# 7_esc.net
KiCad netlist of a schematic drawn in Altium Designer
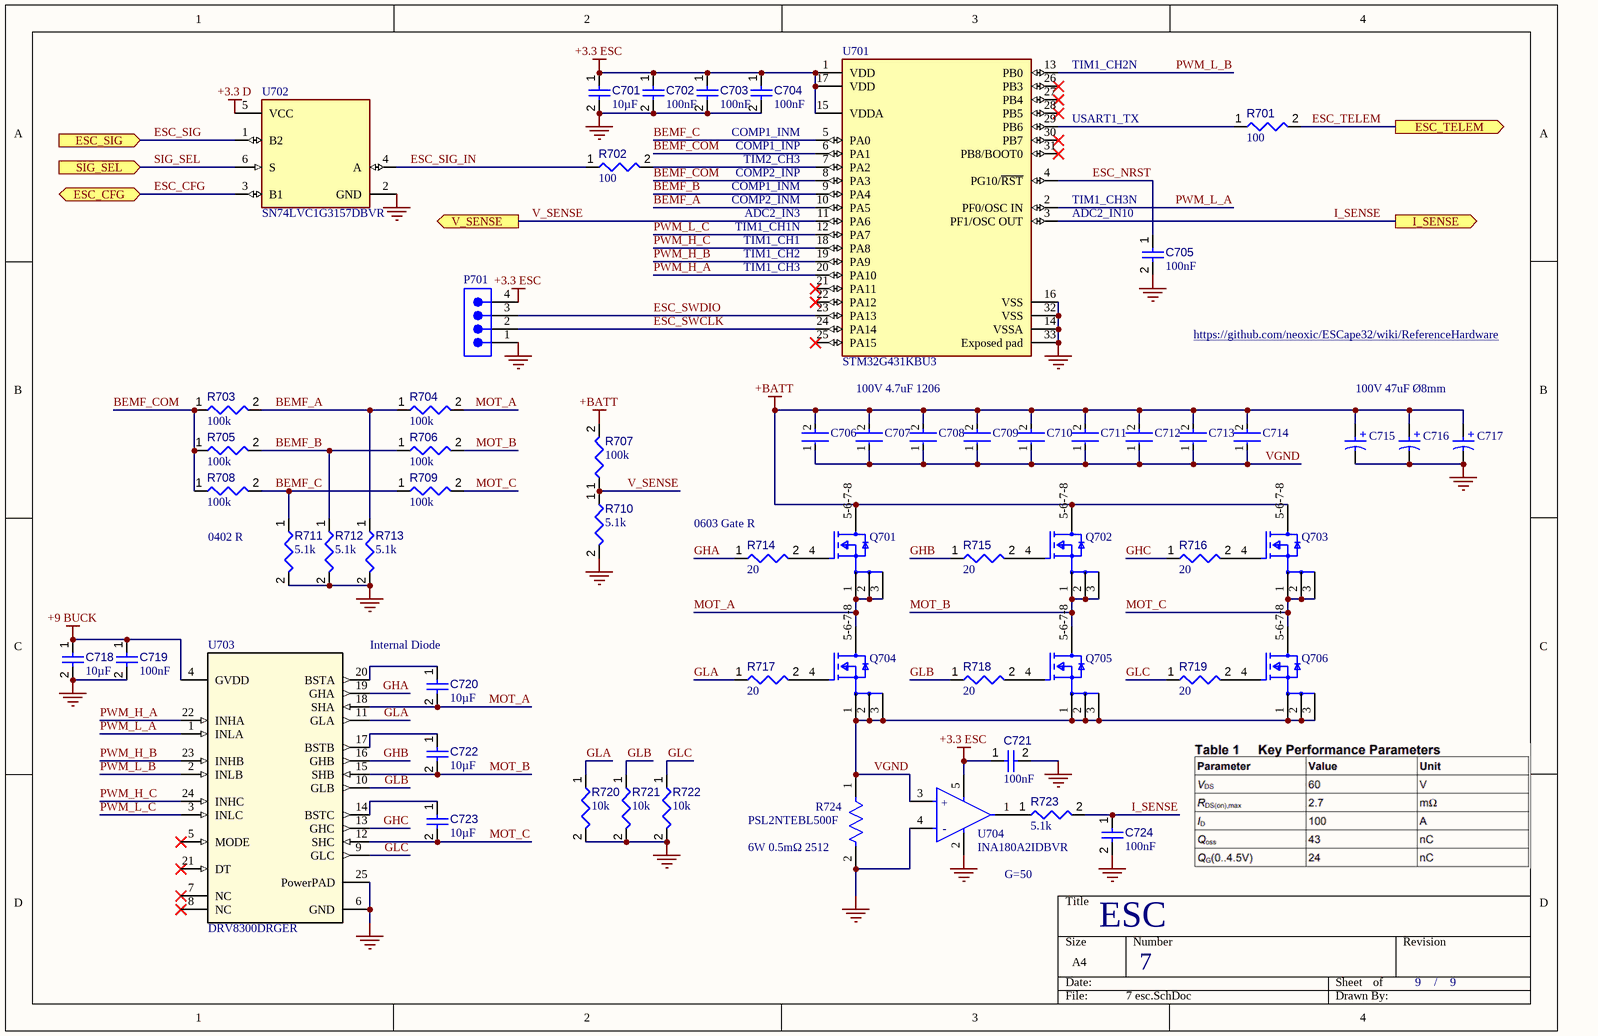
[diagram p0: 7 esc.SchDoc]

(export (version "E")
  (design (tool "Eeschema 10.0.6"))
  (components
    (comp (ref "C701")
      (value "10µF")
      (footprint "CAPC0603(1608)100_L")
      (description "Chip Capacitor, 10µF +/-20%, 10V, 0603, Thickness 1 mm")
      (fields (field (name "TOLERANCE") "10%") (field (name "Comment") "Capacitor 10µF +/-20% 10V 0603"))
      (libsource (lib "UBC Uncrewed Aircraft Systems") (part "CAP-NP-2"))
    )
    (comp (ref "C702")
      (value "100nF")
      (footprint "CAPC0402(1005)60_L")
      (description "Chip Capacitor, 100nF +/-20%, 25V, 0402, Thickness 0.6 mm")
      (fields (field (name "TOLERANCE") "10%") (field (name "Comment") "Capacitor 100nF +/-20% 25V 0402"))
      (libsource (lib "UBC Uncrewed Aircraft Systems") (part "CAP-NP-2"))
    )
    (comp (ref "C703")
      (value "100nF")
      (footprint "CAPC0402(1005)60_L")
      (description "Chip Capacitor, 100nF +/-20%, 25V, 0402, Thickness 0.6 mm")
      (fields (field (name "TOLERANCE") "10%") (field (name "Comment") "Capacitor 100nF +/-20% 25V 0402"))
      (libsource (lib "UBC Uncrewed Aircraft Systems") (part "CAP-NP-2"))
    )
    (comp (ref "C704")
      (value "100nF")
      (footprint "CAPC0402(1005)60_L")
      (description "Chip Capacitor, 100nF +/-20%, 25V, 0402, Thickness 0.6 mm")
      (fields (field (name "TOLERANCE") "10%") (field (name "Comment") "Capacitor 100nF +/-20% 25V 0402"))
      (libsource (lib "UBC Uncrewed Aircraft Systems") (part "CAP-NP-2"))
    )
    (comp (ref "C705")
      (value "100nF")
      (footprint "CAPC0402(1005)60_L")
      (description "Chip Capacitor, 100nF +/-20%, 25V, 0402, Thickness 0.6 mm")
      (fields (field (name "TOLERANCE") "10%") (field (name "Comment") "Capacitor 100nF +/-20% 25V 0402"))
      (libsource (lib "UBC Uncrewed Aircraft Systems") (part "CAP-NP-2"))
    )
    (comp (ref "C706")
      (value "GRM31CZ72A475KE11L")
      (footprint "FP-GRM31C-0_3-e0_3_0_9-MFG")
      (description "Chip Multilayer Ceramic Capacitors for General Purpose, 1206, 4.7uF, X7R, 15%, 10%, 100V")
      (libsource (lib "Altium Content Vault") (part "f23184f103b6ebe33a8c269c53dcba6"))
    )
    (comp (ref "C707")
      (value "GRM31CZ72A475KE11L")
      (footprint "FP-GRM31C-0_3-e0_3_0_9-MFG")
      (description "Chip Multilayer Ceramic Capacitors for General Purpose, 1206, 4.7uF, X7R, 15%, 10%, 100V")
      (libsource (lib "Altium Content Vault") (part "f23184f103b6ebe33a8c269c53dcba6"))
    )
    (comp (ref "C708")
      (value "GRM31CZ72A475KE11L")
      (footprint "FP-GRM31C-0_3-e0_3_0_9-MFG")
      (description "Chip Multilayer Ceramic Capacitors for General Purpose, 1206, 4.7uF, X7R, 15%, 10%, 100V")
      (libsource (lib "Altium Content Vault") (part "f23184f103b6ebe33a8c269c53dcba6"))
    )
    (comp (ref "C709")
      (value "GRM31CZ72A475KE11L")
      (footprint "FP-GRM31C-0_3-e0_3_0_9-MFG")
      (description "Chip Multilayer Ceramic Capacitors for General Purpose, 1206, 4.7uF, X7R, 15%, 10%, 100V")
      (libsource (lib "Altium Content Vault") (part "f23184f103b6ebe33a8c269c53dcba6"))
    )
    (comp (ref "C710")
      (value "GRM31CZ72A475KE11L")
      (footprint "FP-GRM31C-0_3-e0_3_0_9-MFG")
      (description "Chip Multilayer Ceramic Capacitors for General Purpose, 1206, 4.7uF, X7R, 15%, 10%, 100V")
      (libsource (lib "Altium Content Vault") (part "f23184f103b6ebe33a8c269c53dcba6"))
    )
    (comp (ref "C711")
      (value "GRM31CZ72A475KE11L")
      (footprint "FP-GRM31C-0_3-e0_3_0_9-MFG")
      (description "Chip Multilayer Ceramic Capacitors for General Purpose, 1206, 4.7uF, X7R, 15%, 10%, 100V")
      (libsource (lib "Altium Content Vault") (part "f23184f103b6ebe33a8c269c53dcba6"))
    )
    (comp (ref "C712")
      (value "GRM31CZ72A475KE11L")
      (footprint "FP-GRM31C-0_3-e0_3_0_9-MFG")
      (description "Chip Multilayer Ceramic Capacitors for General Purpose, 1206, 4.7uF, X7R, 15%, 10%, 100V")
      (libsource (lib "Altium Content Vault") (part "f23184f103b6ebe33a8c269c53dcba6"))
    )
    (comp (ref "C713")
      (value "GRM31CZ72A475KE11L")
      (footprint "FP-GRM31C-0_3-e0_3_0_9-MFG")
      (description "Chip Multilayer Ceramic Capacitors for General Purpose, 1206, 4.7uF, X7R, 15%, 10%, 100V")
      (libsource (lib "Altium Content Vault") (part "f23184f103b6ebe33a8c269c53dcba6"))
    )
    (comp (ref "C714")
      (value "GRM31CZ72A475KE11L")
      (footprint "FP-GRM31C-0_3-e0_3_0_9-MFG")
      (description "Chip Multilayer Ceramic Capacitors for General Purpose, 1206, 4.7uF, X7R, 15%, 10%, 100V")
      (libsource (lib "Altium Content Vault") (part "f23184f103b6ebe33a8c269c53dcba6"))
    )
    (comp (ref "C715")
      (value "865230453006")
      (footprint "WCAP-AS5H_D8H10.5")
      (description "865230453006 WCAP-AS5H Aluminum Electrolytic Capacitors")
      (fields (field (name "TOLERANCE") "20%"))
      (libsource (lib "Altium Content Vault") (part "Capacitor_Polarized"))
    )
    (comp (ref "C716")
      (value "865230453006")
      (footprint "WCAP-AS5H_D8H10.5")
      (description "865230453006 WCAP-AS5H Aluminum Electrolytic Capacitors")
      (fields (field (name "TOLERANCE") "20%"))
      (libsource (lib "Altium Content Vault") (part "Capacitor_Polarized"))
    )
    (comp (ref "C717")
      (value "865230453006")
      (footprint "WCAP-AS5H_D8H10.5")
      (description "865230453006 WCAP-AS5H Aluminum Electrolytic Capacitors")
      (fields (field (name "TOLERANCE") "20%"))
      (libsource (lib "Altium Content Vault") (part "Capacitor_Polarized"))
    )
    (comp (ref "C718")
      (value "10µF")
      (footprint "CAPC0603(1608)100_L")
      (description "Chip Capacitor, 10µF +/-20%, 10V, 0603, Thickness 1 mm")
      (fields (field (name "TOLERANCE") "10%") (field (name "Comment") "Capacitor 10µF +/-20% 10V 0603"))
      (libsource (lib "UBC Uncrewed Aircraft Systems") (part "CAP-NP-2"))
    )
    (comp (ref "C719")
      (value "100nF")
      (footprint "CAPC0402(1005)60_L")
      (description "Chip Capacitor, 100nF +/-20%, 25V, 0402, Thickness 0.6 mm")
      (fields (field (name "TOLERANCE") "10%") (field (name "Comment") "Capacitor 100nF +/-20% 25V 0402"))
      (libsource (lib "UBC Uncrewed Aircraft Systems") (part "CAP-NP-2"))
    )
    (comp (ref "C720")
      (value "10µF")
      (footprint "CAPC0603(1608)100_L")
      (description "Chip Capacitor, 10µF +/-20%, 10V, 0603, Thickness 1 mm")
      (fields (field (name "TOLERANCE") "10%") (field (name "Comment") "Capacitor 10µF +/-20% 10V 0603"))
      (libsource (lib "UBC Uncrewed Aircraft Systems") (part "CAP-NP-2"))
    )
    (comp (ref "C721")
      (value "100nF")
      (footprint "CAPC0402(1005)60_L")
      (description "Chip Capacitor, 100nF +/-20%, 25V, 0402, Thickness 0.6 mm")
      (fields (field (name "TOLERANCE") "10%") (field (name "Comment") "Capacitor 100nF +/-20% 25V 0402"))
      (libsource (lib "UBC Uncrewed Aircraft Systems") (part "CAP-NP-2"))
    )
    (comp (ref "C722")
      (value "10µF")
      (footprint "CAPC0603(1608)100_L")
      (description "Chip Capacitor, 10µF +/-20%, 10V, 0603, Thickness 1 mm")
      (fields (field (name "TOLERANCE") "10%") (field (name "Comment") "Capacitor 10µF +/-20% 10V 0603"))
      (libsource (lib "UBC Uncrewed Aircraft Systems") (part "CAP-NP-2"))
    )
    (comp (ref "C723")
      (value "10µF")
      (footprint "CAPC0603(1608)100_L")
      (description "Chip Capacitor, 10µF +/-20%, 10V, 0603, Thickness 1 mm")
      (fields (field (name "TOLERANCE") "10%") (field (name "Comment") "Capacitor 10µF +/-20% 10V 0603"))
      (libsource (lib "UBC Uncrewed Aircraft Systems") (part "CAP-NP-2"))
    )
    (comp (ref "C724")
      (value "100nF")
      (footprint "CAPC0402(1005)60_L")
      (description "Chip Capacitor, 100nF +/-20%, 25V, 0402, Thickness 0.6 mm")
      (fields (field (name "TOLERANCE") "10%") (field (name "Comment") "Capacitor 100nF +/-20% 25V 0402"))
      (libsource (lib "UBC Uncrewed Aircraft Systems") (part "CAP-NP-2"))
    )
    (comp (ref "P701")
      (value "61300411121")
      (footprint "61300411121")
      (libsource (lib "Altium Content Vault") (part "Header_Male_1R_04P"))
    )
    (comp (ref "Q701")
      (value "BSC0702LSATMA1")
      (footprint "FP-PG-TDSON-8-MFG")
      (description "BSC0702LSATMA1 Transistor MOSFET N-CH 60V 100A 8-Pin TDSON T/R - Tape and Reel")
      (libsource (lib "Altium Content Vault") (part "02f5e2c6ae375491c3e768752663af3"))
    )
    (comp (ref "Q702")
      (value "BSC0702LSATMA1")
      (footprint "FP-PG-TDSON-8-MFG")
      (description "BSC0702LSATMA1 Transistor MOSFET N-CH 60V 100A 8-Pin TDSON T/R - Tape and Reel")
      (libsource (lib "Altium Content Vault") (part "02f5e2c6ae375491c3e768752663af3"))
    )
    (comp (ref "Q703")
      (value "BSC0702LSATMA1")
      (footprint "FP-PG-TDSON-8-MFG")
      (description "BSC0702LSATMA1 Transistor MOSFET N-CH 60V 100A 8-Pin TDSON T/R - Tape and Reel")
      (libsource (lib "Altium Content Vault") (part "02f5e2c6ae375491c3e768752663af3"))
    )
    (comp (ref "Q704")
      (value "BSC0702LSATMA1")
      (footprint "FP-PG-TDSON-8-MFG")
      (description "BSC0702LSATMA1 Transistor MOSFET N-CH 60V 100A 8-Pin TDSON T/R - Tape and Reel")
      (libsource (lib "Altium Content Vault") (part "02f5e2c6ae375491c3e768752663af3"))
    )
    (comp (ref "Q705")
      (value "BSC0702LSATMA1")
      (footprint "FP-PG-TDSON-8-MFG")
      (description "BSC0702LSATMA1 Transistor MOSFET N-CH 60V 100A 8-Pin TDSON T/R - Tape and Reel")
      (libsource (lib "Altium Content Vault") (part "02f5e2c6ae375491c3e768752663af3"))
    )
    (comp (ref "Q706")
      (value "BSC0702LSATMA1")
      (footprint "FP-PG-TDSON-8-MFG")
      (description "BSC0702LSATMA1 Transistor MOSFET N-CH 60V 100A 8-Pin TDSON T/R - Tape and Reel")
      (libsource (lib "Altium Content Vault") (part "02f5e2c6ae375491c3e768752663af3"))
    )
    (comp (ref "R701")
      (value "100")
      (footprint "RESC0402(1005)_L")
      (description "Chip Resistor, 100 Ohms, +/-1 %, 63 mW, -55 to 155 degC, 0402")
      (fields (field (name "POWER") "63mW") (field (name "TOLERANCE") "1%"))
      (libsource (lib "UBC Uncrewed Aircraft Systems") (part "RES-2"))
    )
    (comp (ref "R702")
      (value "100")
      (footprint "RESC0402(1005)_L")
      (description "Chip Resistor, 100 Ohms, +/-1 %, 63 mW, -55 to 155 degC, 0402")
      (fields (field (name "POWER") "63mW") (field (name "TOLERANCE") "1%"))
      (libsource (lib "UBC Uncrewed Aircraft Systems") (part "RES-2"))
    )
    (comp (ref "R703")
      (value "100k")
      (footprint "RESC0402(1005)_L")
      (description "Chip Resistor, 100 kOhms, +/-1 %, 63 mW, -55 to 155 degC, 0402")
      (fields (field (name "TOLERANCE") "1%") (field (name "POWER") "63mW"))
      (libsource (lib "UBC Uncrewed Aircraft Systems") (part "RES-2"))
    )
    (comp (ref "R704")
      (value "100k")
      (footprint "RESC0402(1005)_L")
      (description "Chip Resistor, 100 kOhms, +/-1 %, 63 mW, -55 to 155 degC, 0402")
      (fields (field (name "TOLERANCE") "1%") (field (name "POWER") "63mW"))
      (libsource (lib "UBC Uncrewed Aircraft Systems") (part "RES-2"))
    )
    (comp (ref "R705")
      (value "100k")
      (footprint "RESC0402(1005)_L")
      (description "Chip Resistor, 100 kOhms, +/-1 %, 63 mW, -55 to 155 degC, 0402")
      (fields (field (name "TOLERANCE") "1%") (field (name "POWER") "63mW"))
      (libsource (lib "UBC Uncrewed Aircraft Systems") (part "RES-2"))
    )
    (comp (ref "R706")
      (value "100k")
      (footprint "RESC0402(1005)_L")
      (description "Chip Resistor, 100 kOhms, +/-1 %, 63 mW, -55 to 155 degC, 0402")
      (fields (field (name "TOLERANCE") "1%") (field (name "POWER") "63mW"))
      (libsource (lib "UBC Uncrewed Aircraft Systems") (part "RES-2"))
    )
    (comp (ref "R707")
      (value "100k")
      (footprint "RESC0402(1005)_L")
      (description "Chip Resistor, 100 kOhms, +/-1 %, 63 mW, -55 to 155 degC, 0402")
      (fields (field (name "TOLERANCE") "1%") (field (name "POWER") "63mW"))
      (libsource (lib "UBC Uncrewed Aircraft Systems") (part "RES-2"))
    )
    (comp (ref "R708")
      (value "100k")
      (footprint "RESC0402(1005)_L")
      (description "Chip Resistor, 100 kOhms, +/-1 %, 63 mW, -55 to 155 degC, 0402")
      (fields (field (name "TOLERANCE") "1%") (field (name "POWER") "63mW"))
      (libsource (lib "UBC Uncrewed Aircraft Systems") (part "RES-2"))
    )
    (comp (ref "R709")
      (value "100k")
      (footprint "RESC0402(1005)_L")
      (description "Chip Resistor, 100 kOhms, +/-1 %, 63 mW, -55 to 155 degC, 0402")
      (fields (field (name "TOLERANCE") "1%") (field (name "POWER") "63mW"))
      (libsource (lib "UBC Uncrewed Aircraft Systems") (part "RES-2"))
    )
    (comp (ref "R710")
      (value "5.1k")
      (footprint "RESC0402(1005)_L")
      (description "Chip Resistor, 5.1 kOhms, +/-1 %, 63 mW, -55 to 155 degC, 0402")
      (fields (field (name "POWER") "63mW") (field (name "TOLERANCE") "1%"))
      (libsource (lib "UBC Uncrewed Aircraft Systems") (part "RES-2"))
    )
    (comp (ref "R711")
      (value "5.1k")
      (footprint "RESC0402(1005)_L")
      (description "Chip Resistor, 5.1 kOhms, +/-1 %, 63 mW, -55 to 155 degC, 0402")
      (fields (field (name "POWER") "63mW") (field (name "TOLERANCE") "1%"))
      (libsource (lib "UBC Uncrewed Aircraft Systems") (part "RES-2"))
    )
    (comp (ref "R712")
      (value "5.1k")
      (footprint "RESC0402(1005)_L")
      (description "Chip Resistor, 5.1 kOhms, +/-1 %, 63 mW, -55 to 155 degC, 0402")
      (fields (field (name "POWER") "63mW") (field (name "TOLERANCE") "1%"))
      (libsource (lib "UBC Uncrewed Aircraft Systems") (part "RES-2"))
    )
    (comp (ref "R713")
      (value "5.1k")
      (footprint "RESC0402(1005)_L")
      (description "Chip Resistor, 5.1 kOhms, +/-1 %, 63 mW, -55 to 155 degC, 0402")
      (fields (field (name "POWER") "63mW") (field (name "TOLERANCE") "1%"))
      (libsource (lib "UBC Uncrewed Aircraft Systems") (part "RES-2"))
    )
    (comp (ref "R714")
      (value "20")
      (footprint "RESC0603(1608)_L")
      (description "Chip Resistor, 20 Ohms, +/-5 %, 0.1 W, -55 to 155 degC, 0603")
      (fields (field (name "TOLERANCE") "5%") (field (name "POWER") "100mW"))
      (libsource (lib "UBC Uncrewed Aircraft Systems") (part "RES-2"))
    )
    (comp (ref "R715")
      (value "20")
      (footprint "RESC0603(1608)_L")
      (description "Chip Resistor, 20 Ohms, +/-5 %, 0.1 W, -55 to 155 degC, 0603")
      (fields (field (name "TOLERANCE") "5%") (field (name "POWER") "100mW"))
      (libsource (lib "UBC Uncrewed Aircraft Systems") (part "RES-2"))
    )
    (comp (ref "R716")
      (value "20")
      (footprint "RESC0603(1608)_L")
      (description "Chip Resistor, 20 Ohms, +/-5 %, 0.1 W, -55 to 155 degC, 0603")
      (fields (field (name "TOLERANCE") "5%") (field (name "POWER") "100mW"))
      (libsource (lib "UBC Uncrewed Aircraft Systems") (part "RES-2"))
    )
    (comp (ref "R717")
      (value "20")
      (footprint "RESC0603(1608)_L")
      (description "Chip Resistor, 20 Ohms, +/-5 %, 0.1 W, -55 to 155 degC, 0603")
      (fields (field (name "TOLERANCE") "5%") (field (name "POWER") "100mW"))
      (libsource (lib "UBC Uncrewed Aircraft Systems") (part "RES-2"))
    )
    (comp (ref "R718")
      (value "20")
      (footprint "RESC0603(1608)_L")
      (description "Chip Resistor, 20 Ohms, +/-5 %, 0.1 W, -55 to 155 degC, 0603")
      (fields (field (name "TOLERANCE") "5%") (field (name "POWER") "100mW"))
      (libsource (lib "UBC Uncrewed Aircraft Systems") (part "RES-2"))
    )
    (comp (ref "R719")
      (value "20")
      (footprint "RESC0603(1608)_L")
      (description "Chip Resistor, 20 Ohms, +/-5 %, 0.1 W, -55 to 155 degC, 0603")
      (fields (field (name "TOLERANCE") "5%") (field (name "POWER") "100mW"))
      (libsource (lib "UBC Uncrewed Aircraft Systems") (part "RES-2"))
    )
    (comp (ref "R720")
      (value "10k")
      (footprint "RESC0402(1005)_L")
      (description "Chip Resistor, 10 kOhms, +/-1 %, 63 mW, -55 to 125 degC, 0402")
      (fields (field (name "POWER") "63mW") (field (name "TOLERANCE") "1%"))
      (libsource (lib "UBC Uncrewed Aircraft Systems") (part "RES-2"))
    )
    (comp (ref "R721")
      (value "10k")
      (footprint "RESC0402(1005)_L")
      (description "Chip Resistor, 10 kOhms, +/-1 %, 63 mW, -55 to 125 degC, 0402")
      (fields (field (name "POWER") "63mW") (field (name "TOLERANCE") "1%"))
      (libsource (lib "UBC Uncrewed Aircraft Systems") (part "RES-2"))
    )
    (comp (ref "R722")
      (value "10k")
      (footprint "RESC0402(1005)_L")
      (description "Chip Resistor, 10 kOhms, +/-1 %, 63 mW, -55 to 125 degC, 0402")
      (fields (field (name "POWER") "63mW") (field (name "TOLERANCE") "1%"))
      (libsource (lib "UBC Uncrewed Aircraft Systems") (part "RES-2"))
    )
    (comp (ref "R723")
      (value "5.1k")
      (footprint "RESC0402(1005)_L")
      (description "Chip Resistor, 5.1 kOhms, +/-1 %, 63 mW, -55 to 155 degC, 0402")
      (fields (field (name "POWER") "63mW") (field (name "TOLERANCE") "1%"))
      (libsource (lib "UBC Uncrewed Aircraft Systems") (part "RES-2"))
    )
    (comp (ref "R724")
      (value "PSL2NTEBL500F")
      (footprint "FP-PSL2NTEBL500F-MFG")
      (description "RES 500 UOHM 1% 8W NONSTANDARD")
      (libsource (lib "Altium Content Vault") (part "1029c3af85768c4190bb7ad29bc67b5"))
    )
    (comp (ref "U701")
      (value "STM32G431KBU3")
      (footprint "FP-UFQFPN32-A0B8-MFG")
      (description "IC MCU 32BIT 128KB FLSH 32UFQFPN")
      (libsource (lib "Altium Content Vault") (part "b0f9ef315fadbc83d4ed39e8b05710e"))
    )
    (comp (ref "U702")
      (value "SN74LVC1G3157DBVR")
      (footprint "FP-DBV0006A-IPC_C")
      (description "IC SWITCH SPDT SOT23-6")
      (libsource (lib "Altium Content Vault") (part "14cfcf06f1431fbc89496e2a44d6624"))
    )
    (comp (ref "U703")
      (value "DRV8300DRGER")
      (footprint "RGE0024B-MFG")
      (description "No Description Available")
      (libsource (lib "DRV8300DRGER") (part "DRV8300DRGER"))
    )
    (comp (ref "U704")
      (value "INA180A2IDBVR")
      (footprint "FP-DBV0005A-MFG")
      (description "IC CURR SENSE 1 CIRCUIT SOT23-5")
      (libsource (lib "Altium Content Vault") (part "0a55cf1a948ad01a3239aec1b7efad0"))
    )
  )
  (nets
    (net (code "1") (name "+3.3 D") (class "Default")
      (node (ref "U702") (pin "5") (pinfunction "VCC_5") (pintype "power_in"))
    )
    (net (code "2") (name "+3.3 ESC") (class "Default")
      (node (ref "C701") (pin "1") (pinfunction "1_1") (pintype "passive"))
      (node (ref "C702") (pin "1") (pinfunction "1_1") (pintype "passive"))
      (node (ref "C703") (pin "1") (pinfunction "1_1") (pintype "passive"))
      (node (ref "C704") (pin "1") (pinfunction "1_1") (pintype "passive"))
      (node (ref "C721") (pin "1") (pinfunction "1_1") (pintype "passive"))
      (node (ref "P701") (pin "4") (pinfunction "4_4") (pintype "passive"))
      (node (ref "U701") (pin "1") (pinfunction "VDD_1") (pintype "power_in"))
      (node (ref "U701") (pin "15") (pinfunction "VDDA_15") (pintype "power_in"))
      (node (ref "U701") (pin "17") (pinfunction "VDD_17") (pintype "power_in"))
      (node (ref "U704") (pin "5") (pinfunction "VS_5") (pintype "power_in"))
    )
    (net (code "3") (name "+9 BUCK") (class "Default")
      (node (ref "C718") (pin "1") (pinfunction "1_1") (pintype "passive"))
      (node (ref "C719") (pin "1") (pinfunction "1_1") (pintype "passive"))
      (node (ref "U703") (pin "4") (pinfunction "GVDD_4") (pintype "power_in"))
    )
    (net (code "4") (name "+BATT") (class "Default")
      (node (ref "C706") (pin "2") (pinfunction "2_2") (pintype "passive"))
      (node (ref "C707") (pin "2") (pinfunction "2_2") (pintype "passive"))
      (node (ref "C708") (pin "2") (pinfunction "2_2") (pintype "passive"))
      (node (ref "C709") (pin "2") (pinfunction "2_2") (pintype "passive"))
      (node (ref "C710") (pin "2") (pinfunction "2_2") (pintype "passive"))
      (node (ref "C711") (pin "2") (pinfunction "2_2") (pintype "passive"))
      (node (ref "C712") (pin "2") (pinfunction "2_2") (pintype "passive"))
      (node (ref "C713") (pin "2") (pinfunction "2_2") (pintype "passive"))
      (node (ref "C714") (pin "2") (pinfunction "2_2") (pintype "passive"))
      (node (ref "C715") (pin "1") (pinfunction "P_1") (pintype "passive"))
      (node (ref "C716") (pin "1") (pinfunction "P_1") (pintype "passive"))
      (node (ref "C717") (pin "1") (pinfunction "P_1") (pintype "passive"))
      (node (ref "Q701") (pin "5-6-7-8") (pinfunction "Drain_5-6-7-8") (pintype "passive"))
      (node (ref "Q702") (pin "5-6-7-8") (pinfunction "Drain_5-6-7-8") (pintype "passive"))
      (node (ref "Q703") (pin "5-6-7-8") (pinfunction "Drain_5-6-7-8") (pintype "passive"))
      (node (ref "R707") (pin "2") (pinfunction "2_2") (pintype "passive"))
    )
    (net (code "5") (name "/BEMF_A") (class "Default")
      (node (ref "R703") (pin "2") (pinfunction "2_2") (pintype "passive"))
      (node (ref "R704") (pin "1") (pinfunction "1_1") (pintype "passive"))
      (node (ref "R713") (pin "1") (pinfunction "1_1") (pintype "passive"))
      (node (ref "U701") (pin "10") (pinfunction "PA5_10") (pintype "bidirectional"))
    )
    (net (code "6") (name "/BEMF_B") (class "Default")
      (node (ref "R705") (pin "2") (pinfunction "2_2") (pintype "passive"))
      (node (ref "R706") (pin "1") (pinfunction "1_1") (pintype "passive"))
      (node (ref "R712") (pin "1") (pinfunction "1_1") (pintype "passive"))
      (node (ref "U701") (pin "9") (pinfunction "PA4_9") (pintype "bidirectional"))
    )
    (net (code "7") (name "/BEMF_C") (class "Default")
      (node (ref "R708") (pin "2") (pinfunction "2_2") (pintype "passive"))
      (node (ref "R709") (pin "1") (pinfunction "1_1") (pintype "passive"))
      (node (ref "R711") (pin "1") (pinfunction "1_1") (pintype "passive"))
      (node (ref "U701") (pin "5") (pinfunction "PA0_5") (pintype "bidirectional"))
    )
    (net (code "8") (name "/BEMF_COM") (class "Default")
      (node (ref "R703") (pin "1") (pinfunction "1_1") (pintype "passive"))
      (node (ref "R705") (pin "1") (pinfunction "1_1") (pintype "passive"))
      (node (ref "R708") (pin "1") (pinfunction "1_1") (pintype "passive"))
      (node (ref "U701") (pin "6") (pinfunction "PA1_6") (pintype "bidirectional"))
      (node (ref "U701") (pin "8") (pinfunction "PA3_8") (pintype "bidirectional"))
    )
    (net (code "9") (name "/ESC_CFG") (class "Default")
      (node (ref "U702") (pin "3") (pinfunction "B1_3") (pintype "bidirectional"))
    )
    (net (code "10") (name "/ESC_NRST") (class "Default")
      (node (ref "C705") (pin "1") (pinfunction "1_1") (pintype "passive"))
      (node (ref "U701") (pin "4") (pinfunction "PG10/~{RST}_4") (pintype "bidirectional"))
    )
    (net (code "11") (name "/ESC_SIG") (class "Default")
      (node (ref "U702") (pin "1") (pinfunction "B2_1") (pintype "bidirectional"))
    )
    (net (code "12") (name "/ESC_SIG_IN") (class "Default")
      (node (ref "R702") (pin "1") (pinfunction "1_1") (pintype "passive"))
      (node (ref "U702") (pin "4") (pinfunction "A_4") (pintype "bidirectional"))
    )
    (net (code "13") (name "/ESC_SWCLK") (class "Default")
      (node (ref "P701") (pin "2") (pinfunction "2_2") (pintype "passive"))
      (node (ref "U701") (pin "24") (pinfunction "PA14_24") (pintype "bidirectional"))
    )
    (net (code "14") (name "/ESC_SWDIO") (class "Default")
      (node (ref "P701") (pin "3") (pinfunction "3_3") (pintype "passive"))
      (node (ref "U701") (pin "23") (pinfunction "PA13_23") (pintype "bidirectional"))
    )
    (net (code "15") (name "/ESC_TELEM") (class "Default")
      (node (ref "R701") (pin "2") (pinfunction "2_2") (pintype "passive"))
    )
    (net (code "16") (name "/GHA") (class "Default")
      (node (ref "R714") (pin "1") (pinfunction "1_1") (pintype "passive"))
      (node (ref "U703") (pin "19") (pinfunction "GHA_19") (pintype "output"))
    )
    (net (code "17") (name "/GHB") (class "Default")
      (node (ref "R715") (pin "1") (pinfunction "1_1") (pintype "passive"))
      (node (ref "U703") (pin "16") (pinfunction "GHB_16") (pintype "output"))
    )
    (net (code "18") (name "/GHC") (class "Default")
      (node (ref "R716") (pin "1") (pinfunction "1_1") (pintype "passive"))
      (node (ref "U703") (pin "13") (pinfunction "GHC_13") (pintype "output"))
    )
    (net (code "19") (name "/GLA") (class "Default")
      (node (ref "R717") (pin "1") (pinfunction "1_1") (pintype "passive"))
      (node (ref "R720") (pin "1") (pinfunction "1_1") (pintype "passive"))
      (node (ref "U703") (pin "11") (pinfunction "GLA_11") (pintype "output"))
    )
    (net (code "20") (name "/GLB") (class "Default")
      (node (ref "R718") (pin "1") (pinfunction "1_1") (pintype "passive"))
      (node (ref "R721") (pin "1") (pinfunction "1_1") (pintype "passive"))
      (node (ref "U703") (pin "10") (pinfunction "GLB_10") (pintype "output"))
    )
    (net (code "21") (name "/GLC") (class "Default")
      (node (ref "R719") (pin "1") (pinfunction "1_1") (pintype "passive"))
      (node (ref "R722") (pin "1") (pinfunction "1_1") (pintype "passive"))
      (node (ref "U703") (pin "9") (pinfunction "GLC_9") (pintype "output"))
    )
    (net (code "22") (name "/I_SENSE") (class "Default")
      (node (ref "C724") (pin "1") (pinfunction "1_1") (pintype "passive"))
      (node (ref "R723") (pin "2") (pinfunction "2_2") (pintype "passive"))
      (node (ref "U701") (pin "3") (pinfunction "PF1/OSC_OUT_3") (pintype "bidirectional"))
    )
    (net (code "23") (name "/MOT_A") (class "Default")
      (node (ref "C720") (pin "2") (pinfunction "2_2") (pintype "passive"))
      (node (ref "Q701") (pin "1") (pinfunction "Source_1") (pintype "passive"))
      (node (ref "Q701") (pin "2") (pinfunction "Source_2") (pintype "passive"))
      (node (ref "Q701") (pin "3") (pinfunction "Source_3") (pintype "passive"))
      (node (ref "Q704") (pin "5-6-7-8") (pinfunction "Drain_5-6-7-8") (pintype "passive"))
      (node (ref "R704") (pin "2") (pinfunction "2_2") (pintype "passive"))
      (node (ref "U703") (pin "18") (pinfunction "SHA_18") (pintype "input"))
    )
    (net (code "24") (name "/MOT_B") (class "Default")
      (node (ref "C722") (pin "2") (pinfunction "2_2") (pintype "passive"))
      (node (ref "Q702") (pin "1") (pinfunction "Source_1") (pintype "passive"))
      (node (ref "Q702") (pin "2") (pinfunction "Source_2") (pintype "passive"))
      (node (ref "Q702") (pin "3") (pinfunction "Source_3") (pintype "passive"))
      (node (ref "Q705") (pin "5-6-7-8") (pinfunction "Drain_5-6-7-8") (pintype "passive"))
      (node (ref "R706") (pin "2") (pinfunction "2_2") (pintype "passive"))
      (node (ref "U703") (pin "15") (pinfunction "SHB_15") (pintype "input"))
    )
    (net (code "25") (name "/MOT_C") (class "Default")
      (node (ref "C723") (pin "2") (pinfunction "2_2") (pintype "passive"))
      (node (ref "Q703") (pin "1") (pinfunction "Source_1") (pintype "passive"))
      (node (ref "Q703") (pin "2") (pinfunction "Source_2") (pintype "passive"))
      (node (ref "Q703") (pin "3") (pinfunction "Source_3") (pintype "passive"))
      (node (ref "Q706") (pin "5-6-7-8") (pinfunction "Drain_5-6-7-8") (pintype "passive"))
      (node (ref "R709") (pin "2") (pinfunction "2_2") (pintype "passive"))
      (node (ref "U703") (pin "12") (pinfunction "SHC_12") (pintype "input"))
    )
    (net (code "26") (name "/PWM_H_A") (class "Default")
      (node (ref "U701") (pin "20") (pinfunction "PA10_20") (pintype "bidirectional"))
      (node (ref "U703") (pin "22") (pinfunction "INHA_22") (pintype "input"))
    )
    (net (code "27") (name "/PWM_H_B") (class "Default")
      (node (ref "U701") (pin "19") (pinfunction "PA9_19") (pintype "bidirectional"))
      (node (ref "U703") (pin "23") (pinfunction "INHB_23") (pintype "input"))
    )
    (net (code "28") (name "/PWM_H_C") (class "Default")
      (node (ref "U701") (pin "18") (pinfunction "PA8_18") (pintype "bidirectional"))
      (node (ref "U703") (pin "24") (pinfunction "INHC_24") (pintype "input"))
    )
    (net (code "29") (name "/PWM_L_A") (class "Default")
      (node (ref "U701") (pin "2") (pinfunction "PF0/OSC_IN_2") (pintype "bidirectional"))
      (node (ref "U703") (pin "1") (pinfunction "INLA_1") (pintype "input"))
    )
    (net (code "30") (name "/PWM_L_B") (class "Default")
      (node (ref "U701") (pin "13") (pinfunction "PB0_13") (pintype "bidirectional"))
      (node (ref "U703") (pin "2") (pinfunction "INLB_2") (pintype "input"))
    )
    (net (code "31") (name "/PWM_L_C") (class "Default")
      (node (ref "U701") (pin "12") (pinfunction "PA7_12") (pintype "bidirectional"))
      (node (ref "U703") (pin "3") (pinfunction "INLC_3") (pintype "input"))
    )
    (net (code "32") (name "/SIG_SEL") (class "Default")
      (node (ref "U702") (pin "6") (pinfunction "S_6") (pintype "input"))
    )
    (net (code "33") (name "/VGND") (class "Default")
      (node (ref "C706") (pin "1") (pinfunction "1_1") (pintype "passive"))
      (node (ref "C707") (pin "1") (pinfunction "1_1") (pintype "passive"))
      (node (ref "C708") (pin "1") (pinfunction "1_1") (pintype "passive"))
      (node (ref "C709") (pin "1") (pinfunction "1_1") (pintype "passive"))
      (node (ref "C710") (pin "1") (pinfunction "1_1") (pintype "passive"))
      (node (ref "C711") (pin "1") (pinfunction "1_1") (pintype "passive"))
      (node (ref "C712") (pin "1") (pinfunction "1_1") (pintype "passive"))
      (node (ref "C713") (pin "1") (pinfunction "1_1") (pintype "passive"))
      (node (ref "C714") (pin "1") (pinfunction "1_1") (pintype "passive"))
      (node (ref "Q704") (pin "1") (pinfunction "Source_1") (pintype "passive"))
      (node (ref "Q704") (pin "2") (pinfunction "Source_2") (pintype "passive"))
      (node (ref "Q704") (pin "3") (pinfunction "Source_3") (pintype "passive"))
      (node (ref "Q705") (pin "1") (pinfunction "Source_1") (pintype "passive"))
      (node (ref "Q705") (pin "2") (pinfunction "Source_2") (pintype "passive"))
      (node (ref "Q705") (pin "3") (pinfunction "Source_3") (pintype "passive"))
      (node (ref "Q706") (pin "1") (pinfunction "Source_1") (pintype "passive"))
      (node (ref "Q706") (pin "2") (pinfunction "Source_2") (pintype "passive"))
      (node (ref "Q706") (pin "3") (pinfunction "Source_3") (pintype "passive"))
      (node (ref "R724") (pin "1") (pinfunction "1_1") (pintype "passive"))
      (node (ref "U704") (pin "3") (pinfunction "IN+_3") (pintype "tri_state"))
    )
    (net (code "34") (name "/V_SENSE") (class "Default")
      (node (ref "R707") (pin "1") (pinfunction "1_1") (pintype "passive"))
      (node (ref "R710") (pin "1") (pinfunction "1_1") (pintype "passive"))
      (node (ref "U701") (pin "11") (pinfunction "PA6_11") (pintype "bidirectional"))
    )
    (net (code "35") (name "GND") (class "Default")
      (node (ref "C701") (pin "2") (pinfunction "2_2") (pintype "passive"))
      (node (ref "C702") (pin "2") (pinfunction "2_2") (pintype "passive"))
      (node (ref "C703") (pin "2") (pinfunction "2_2") (pintype "passive"))
      (node (ref "C704") (pin "2") (pinfunction "2_2") (pintype "passive"))
      (node (ref "C705") (pin "2") (pinfunction "2_2") (pintype "passive"))
      (node (ref "C715") (pin "2") (pinfunction "N_2") (pintype "passive"))
      (node (ref "C716") (pin "2") (pinfunction "N_2") (pintype "passive"))
      (node (ref "C717") (pin "2") (pinfunction "N_2") (pintype "passive"))
      (node (ref "C718") (pin "2") (pinfunction "2_2") (pintype "passive"))
      (node (ref "C719") (pin "2") (pinfunction "2_2") (pintype "passive"))
      (node (ref "C721") (pin "2") (pinfunction "2_2") (pintype "passive"))
      (node (ref "C724") (pin "2") (pinfunction "2_2") (pintype "passive"))
      (node (ref "P701") (pin "1") (pinfunction "1_1") (pintype "passive"))
      (node (ref "R710") (pin "2") (pinfunction "2_2") (pintype "passive"))
      (node (ref "R711") (pin "2") (pinfunction "2_2") (pintype "passive"))
      (node (ref "R712") (pin "2") (pinfunction "2_2") (pintype "passive"))
      (node (ref "R713") (pin "2") (pinfunction "2_2") (pintype "passive"))
      (node (ref "R720") (pin "2") (pinfunction "2_2") (pintype "passive"))
      (node (ref "R721") (pin "2") (pinfunction "2_2") (pintype "passive"))
      (node (ref "R722") (pin "2") (pinfunction "2_2") (pintype "passive"))
      (node (ref "R724") (pin "2") (pinfunction "2_2") (pintype "passive"))
      (node (ref "U701") (pin "14") (pinfunction "VSSA_14") (pintype "power_in"))
      (node (ref "U701") (pin "16") (pinfunction "VSS_16") (pintype "power_in"))
      (node (ref "U701") (pin "32") (pinfunction "VSS_32") (pintype "power_in"))
      (node (ref "U701") (pin "33") (pinfunction "Exposed_pad_33") (pintype "power_in"))
      (node (ref "U702") (pin "2") (pinfunction "GND_2") (pintype "power_in"))
      (node (ref "U703") (pin "25") (pinfunction "PowerPAD_25") (pintype "power_in"))
      (node (ref "U703") (pin "6") (pinfunction "GND_6") (pintype "power_in"))
      (node (ref "U704") (pin "2") (pinfunction "GND_2") (pintype "power_in"))
      (node (ref "U704") (pin "4") (pinfunction "IN-_4") (pintype "tri_state"))
    )
    (net (code "36") (name "Net-(Q701-Gate)") (class "Default")
      (node (ref "Q701") (pin "4") (pinfunction "Gate_4") (pintype "passive"))
      (node (ref "R714") (pin "2") (pinfunction "2_2") (pintype "passive"))
    )
    (net (code "37") (name "Net-(Q702-Gate)") (class "Default")
      (node (ref "Q702") (pin "4") (pinfunction "Gate_4") (pintype "passive"))
      (node (ref "R715") (pin "2") (pinfunction "2_2") (pintype "passive"))
    )
    (net (code "38") (name "Net-(Q703-Gate)") (class "Default")
      (node (ref "Q703") (pin "4") (pinfunction "Gate_4") (pintype "passive"))
      (node (ref "R716") (pin "2") (pinfunction "2_2") (pintype "passive"))
    )
    (net (code "39") (name "Net-(Q704-Gate)") (class "Default")
      (node (ref "Q704") (pin "4") (pinfunction "Gate_4") (pintype "passive"))
      (node (ref "R717") (pin "2") (pinfunction "2_2") (pintype "passive"))
    )
    (net (code "40") (name "Net-(Q705-Gate)") (class "Default")
      (node (ref "Q705") (pin "4") (pinfunction "Gate_4") (pintype "passive"))
      (node (ref "R718") (pin "2") (pinfunction "2_2") (pintype "passive"))
    )
    (net (code "41") (name "Net-(Q706-Gate)") (class "Default")
      (node (ref "Q706") (pin "4") (pinfunction "Gate_4") (pintype "passive"))
      (node (ref "R719") (pin "2") (pinfunction "2_2") (pintype "passive"))
    )
    (net (code "42") (name "Net-(U701-PA2)") (class "Default")
      (node (ref "R702") (pin "2") (pinfunction "2_2") (pintype "passive"))
      (node (ref "U701") (pin "7") (pinfunction "PA2_7") (pintype "bidirectional"))
    )
    (net (code "43") (name "Net-(U701-PB6)") (class "Default")
      (node (ref "R701") (pin "1") (pinfunction "1_1") (pintype "passive"))
      (node (ref "U701") (pin "29") (pinfunction "PB6_29") (pintype "bidirectional"))
    )
    (net (code "44") (name "Net-(U703-BSTA)") (class "Default")
      (node (ref "C720") (pin "1") (pinfunction "1_1") (pintype "passive"))
      (node (ref "U703") (pin "20") (pinfunction "BSTA_20") (pintype "output"))
    )
    (net (code "45") (name "Net-(U703-BSTB)") (class "Default")
      (node (ref "C722") (pin "1") (pinfunction "1_1") (pintype "passive"))
      (node (ref "U703") (pin "17") (pinfunction "BSTB_17") (pintype "output"))
    )
    (net (code "46") (name "Net-(U703-BSTC)") (class "Default")
      (node (ref "C723") (pin "1") (pinfunction "1_1") (pintype "passive"))
      (node (ref "U703") (pin "14") (pinfunction "BSTC_14") (pintype "output"))
    )
    (net (code "47") (name "Net-(U704-OUT)") (class "Default")
      (node (ref "R723") (pin "1") (pinfunction "1_1") (pintype "passive"))
      (node (ref "U704") (pin "1") (pinfunction "OUT_1") (pintype "passive"))
    )
    (net (code "48") (name "unconnected-(U701-PA11-Pad21)") (class "Default")
      (node (ref "U701") (pin "21") (pinfunction "PA11_21") (pintype "bidirectional+no_connect"))
    )
    (net (code "49") (name "unconnected-(U701-PA12-Pad22)") (class "Default")
      (node (ref "U701") (pin "22") (pinfunction "PA12_22") (pintype "bidirectional+no_connect"))
    )
    (net (code "50") (name "unconnected-(U701-PA15-Pad25)") (class "Default")
      (node (ref "U701") (pin "25") (pinfunction "PA15_25") (pintype "bidirectional+no_connect"))
    )
    (net (code "51") (name "unconnected-(U701-PB3-Pad26)") (class "Default")
      (node (ref "U701") (pin "26") (pinfunction "PB3_26") (pintype "bidirectional+no_connect"))
    )
    (net (code "52") (name "unconnected-(U701-PB4-Pad27)") (class "Default")
      (node (ref "U701") (pin "27") (pinfunction "PB4_27") (pintype "bidirectional+no_connect"))
    )
    (net (code "53") (name "unconnected-(U701-PB5-Pad28)") (class "Default")
      (node (ref "U701") (pin "28") (pinfunction "PB5_28") (pintype "bidirectional+no_connect"))
    )
    (net (code "54") (name "unconnected-(U701-PB7-Pad30)") (class "Default")
      (node (ref "U701") (pin "30") (pinfunction "PB7_30") (pintype "bidirectional+no_connect"))
    )
    (net (code "55") (name "unconnected-(U701-PB8{slash}BOOT0-Pad31)") (class "Default")
      (node (ref "U701") (pin "31") (pinfunction "PB8/BOOT0_31") (pintype "bidirectional+no_connect"))
    )
    (net (code "56") (name "unconnected-(U703-DT-Pad21)") (class "Default")
      (node (ref "U703") (pin "21") (pinfunction "DT_21") (pintype "input+no_connect"))
    )
    (net (code "57") (name "unconnected-(U703-MODE-Pad5)") (class "Default")
      (node (ref "U703") (pin "5") (pinfunction "MODE_5") (pintype "input+no_connect"))
    )
    (net (code "58") (name "unconnected-(U703-NC-Pad7)") (class "Default")
      (node (ref "U703") (pin "7") (pinfunction "NC_7") (pintype "passive+no_connect"))
    )
    (net (code "59") (name "unconnected-(U703-NC-Pad8)") (class "Default")
      (node (ref "U703") (pin "8") (pinfunction "NC_8") (pintype "passive+no_connect"))
    )
  )
)
